# CC-S03-V00-CANBUS.net
KiCad netlist of a schematic drawn in Altium Designer
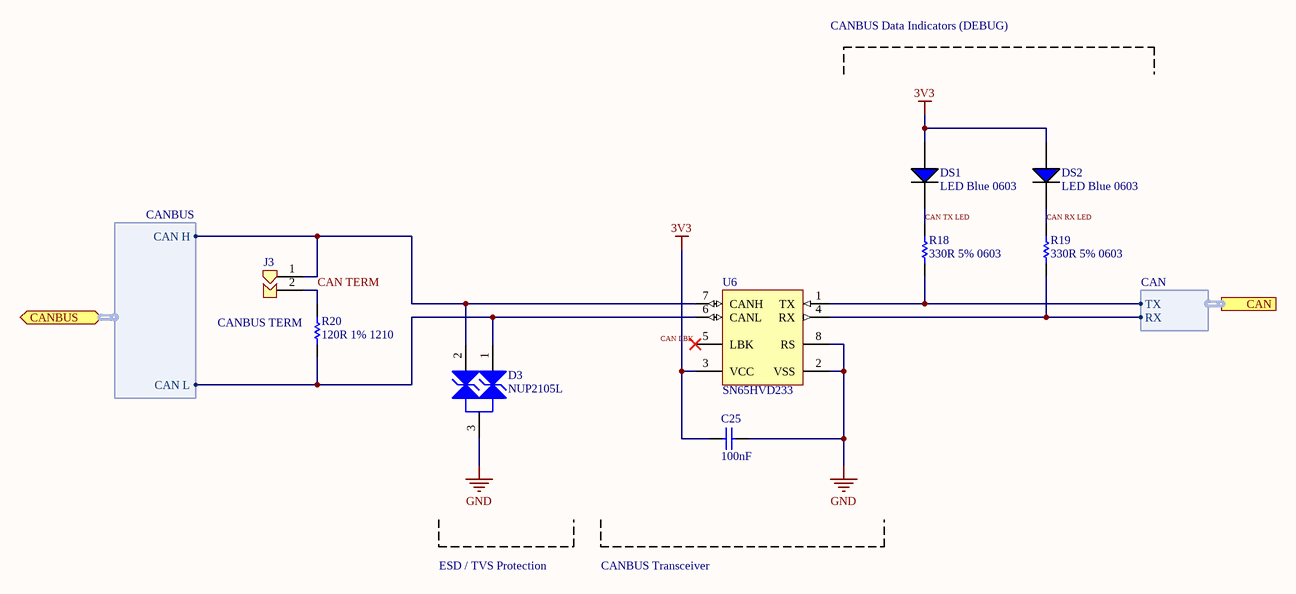
[diagram p0: CC-S03-V00-CANBUS.SchDoc]

(export (version "E")
  (design (tool "Eeschema 10.0.6"))
  (components
    (comp (ref "C25")
      (value "100nF")
      (footprint "Cap_Ceramic_0603")
      (description "Capacitor, Ceramic, SMD, 100nF, 50V, 5%, X7R, 0603")
      (libsource (lib "StandardCapacitors") (part "100nF 50V 5% X7R 0603"))
    )
    (comp (ref "D3")
      (value "NUP2105L")
      (footprint "NUP2105L")
      (libsource (lib "QUTMS_CANLibrary") (part "NUP2105L"))
    )
    (comp (ref "DS1")
      (value "LED Blue 0603")
      (footprint "LED BLUE 0603")
      (libsource (lib "QUTMS_LEDLibrary") (part "LED BLUE 0603"))
    )
    (comp (ref "DS2")
      (value "LED Blue 0603")
      (footprint "LED BLUE 0603")
      (libsource (lib "QUTMS_LEDLibrary") (part "LED BLUE 0603"))
    )
    (comp (ref "J3")
      (value "Jumper 2Way Solderable")
      (footprint "Jumper_2Way_Solderable")
      (description "Jumper 2Way Side Solderable")
      (libsource (lib "QUTMS_JumperLibrary") (part "Jumper 2Way Side Solderable"))
    )
    (comp (ref "R18")
      (value "330R 5% 0603")
      (footprint "Res_ThinFilm_0603")
      (description "Resistor, SMD, 330R, 0.1W, 5%, 0603")
      (libsource (lib "StandardResistors") (part "330R 5% 0603"))
    )
    (comp (ref "R19")
      (value "330R 5% 0603")
      (footprint "Res_ThinFilm_0603")
      (description "Resistor, SMD, 330R, 0.1W, 5%, 0603")
      (libsource (lib "StandardResistors") (part "330R 5% 0603"))
    )
    (comp (ref "R20")
      (value "120R 1% 1210")
      (footprint "Res_ThinFilm_1210")
      (description "Resistor, SMD, 120R, 0.25W, 1%, 1210")
      (libsource (lib "StandardResistors") (part "120R 1% 1210"))
    )
    (comp (ref "U6")
      (value "SN65HVD233")
      (footprint "SN65HVD233DR")
      (libsource (lib "QUTMS_CANLibrary") (part "SN65HVD233"))
    )
  )
  (nets
    (net (code "3") (name "/CAN LBK") (class "Default")
      (node (ref "U6") (pin "5") (pinfunction "LBK_5") (pintype "passive+no_connect"))
    )
    (net (code "4") (name "/CAN RX LED") (class "Default")
      (node (ref "DS2") (pin "2") (pinfunction "C_2") (pintype "passive"))
      (node (ref "R19") (pin "2") (pinfunction "2_2") (pintype "passive"))
    )
    (net (code "5") (name "/CAN TERM") (class "Default")
      (node (ref "J3") (pin "2") (pinfunction "2_2") (pintype "passive"))
      (node (ref "R20") (pin "2") (pinfunction "2_2") (pintype "passive"))
    )
    (net (code "6") (name "/CAN TX LED") (class "Default")
      (node (ref "DS1") (pin "2") (pinfunction "C_2") (pintype "passive"))
      (node (ref "R18") (pin "2") (pinfunction "2_2") (pintype "passive"))
    )
    (net (code "9") (name "3V3") (class "Default")
      (node (ref "C25") (pin "2") (pinfunction "2_2") (pintype "passive"))
      (node (ref "DS1") (pin "1") (pinfunction "A_1") (pintype "passive"))
      (node (ref "DS2") (pin "1") (pinfunction "A_1") (pintype "passive"))
      (node (ref "U6") (pin "3") (pinfunction "VCC_3") (pintype "passive"))
    )
    (net (code "10") (name "GND") (class "Default")
      (node (ref "C25") (pin "1") (pinfunction "1_1") (pintype "passive"))
      (node (ref "D3") (pin "3") (pinfunction "3_3") (pintype "passive"))
      (node (ref "U6") (pin "2") (pinfunction "VSS_2") (pintype "passive"))
      (node (ref "U6") (pin "8") (pinfunction "RS_8") (pintype "passive"))
    )
    (net (code "11") (name "Net-(U6-CANH)") (class "Default")
      (node (ref "D3") (pin "2") (pinfunction "2_2") (pintype "passive"))
      (node (ref "J3") (pin "1") (pinfunction "1_1") (pintype "passive"))
      (node (ref "U6") (pin "7") (pinfunction "CANH_7") (pintype "bidirectional"))
    )
    (net (code "12") (name "Net-(U6-CANL)") (class "Default")
      (node (ref "D3") (pin "1") (pinfunction "1_1") (pintype "passive"))
      (node (ref "R20") (pin "1") (pinfunction "1_1") (pintype "passive"))
      (node (ref "U6") (pin "6") (pinfunction "CANL_6") (pintype "bidirectional"))
    )
    (net (code "13") (name "Net-(U6-RX)") (class "Default")
      (node (ref "R19") (pin "1") (pinfunction "1_1") (pintype "passive"))
      (node (ref "U6") (pin "4") (pinfunction "RX_4") (pintype "output"))
    )
    (net (code "14") (name "Net-(U6-TX)") (class "Default")
      (node (ref "R18") (pin "1") (pinfunction "1_1") (pintype "passive"))
      (node (ref "U6") (pin "1") (pinfunction "TX_1") (pintype "input"))
    )
  )
)
